# motor_kontrol_v1.net
KiCad netlist of a schematic drawn in EAGLE
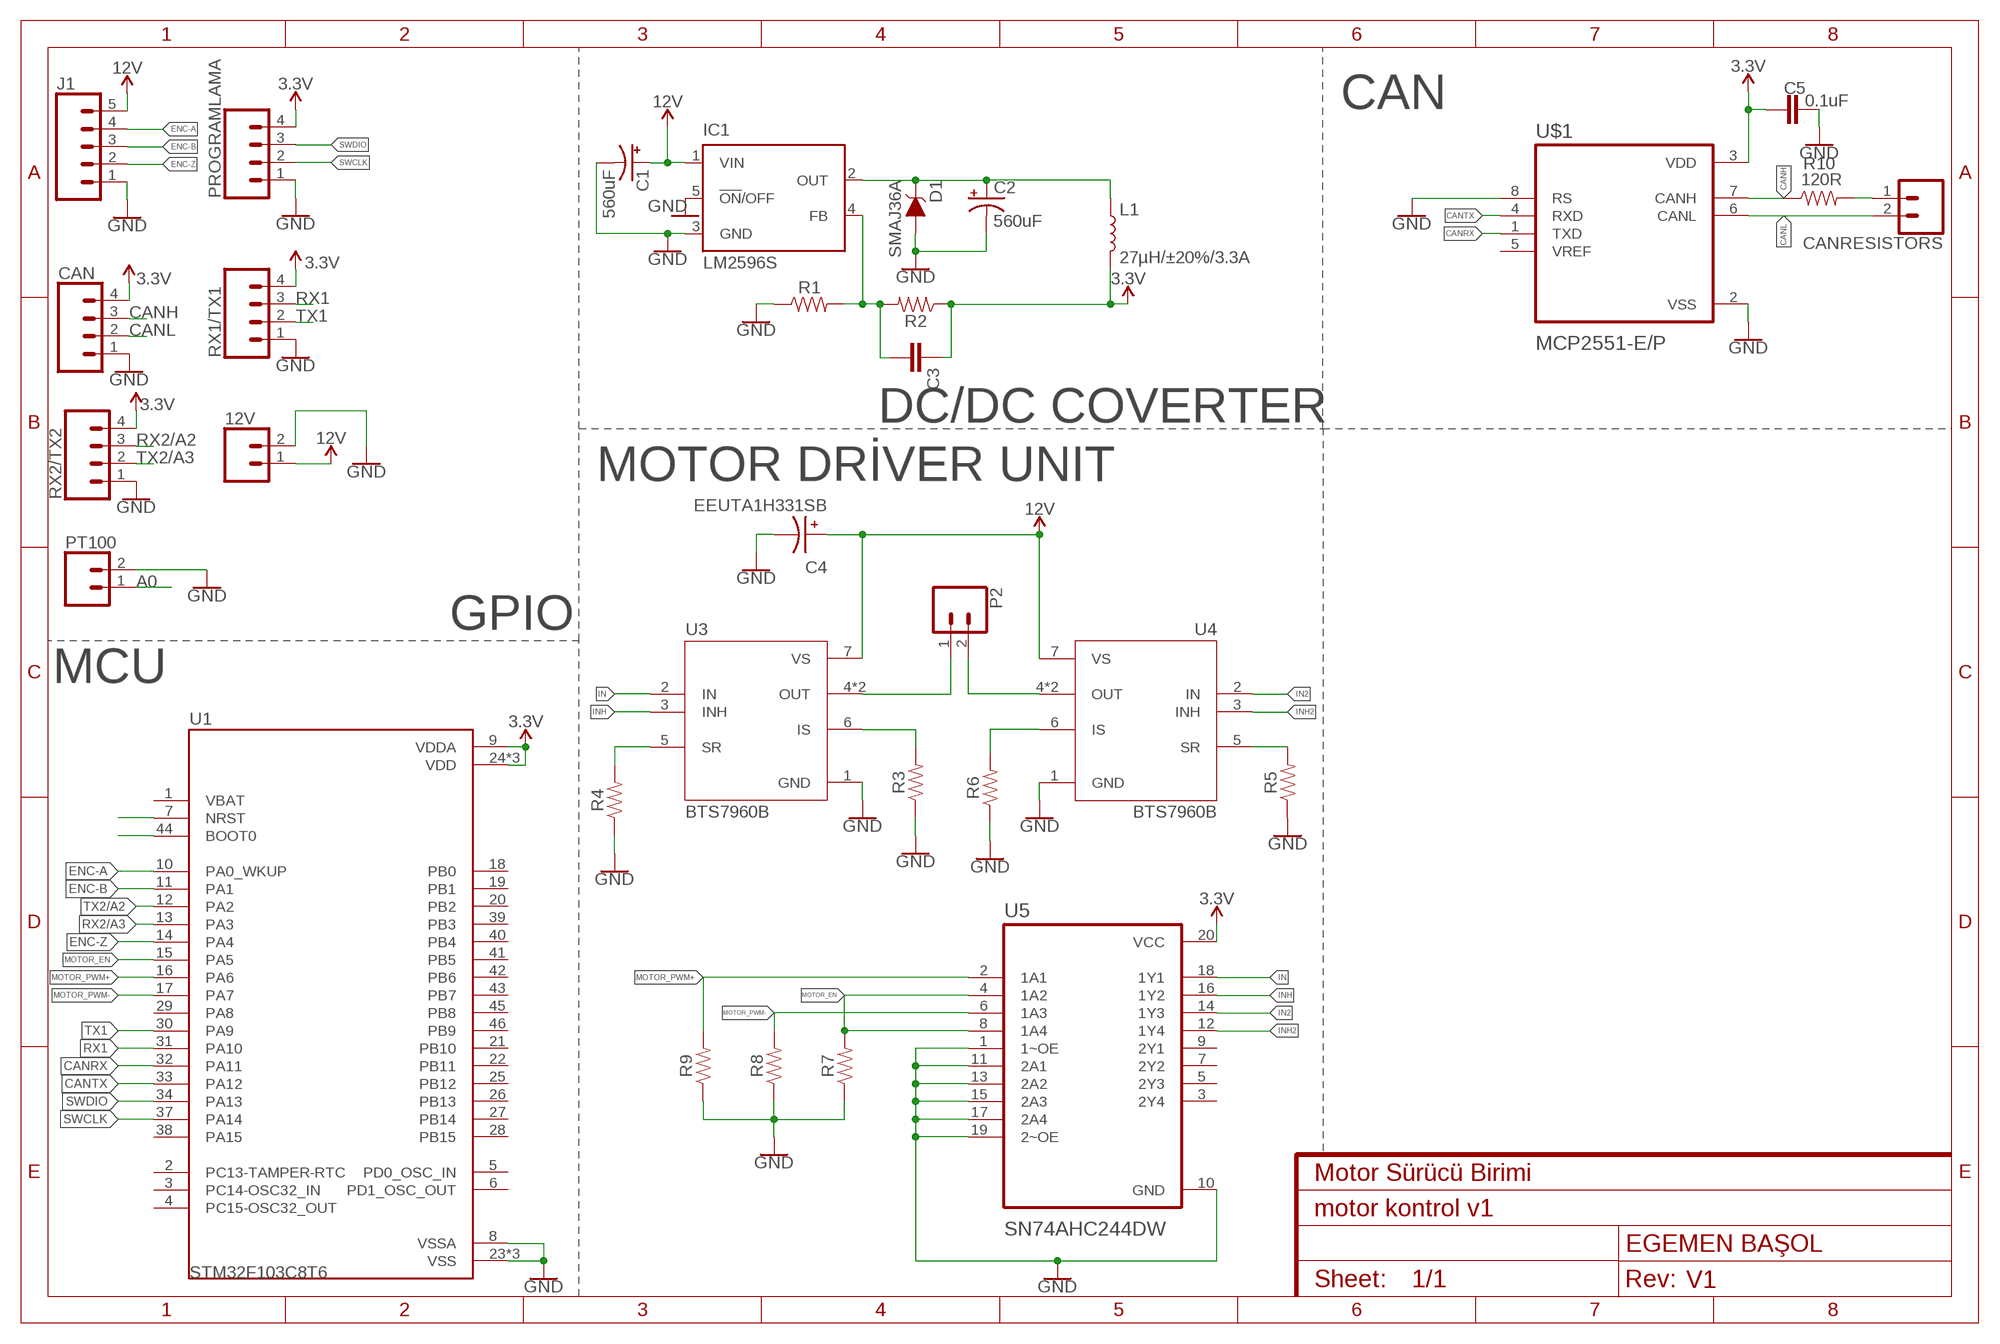
[diagram p0: schematic, sheet 1]

(export (version "E")
  (design (tool "Eeschema 10.0.6"))
  (components
    (comp (ref "12V")
      (value "CONN_023.5MM_LOCK")
      (footprint "eagle-import:SCREWTERMINAL-3.5MM-2_LOCK")
      (libsource (lib "eagle-import") (part "CONN_023.5MM_LOCK"))
    )
    (comp (ref "C1")
      (value "560uF")
      (footprint "eagle-import:PANASONIC_G")
      (libsource (lib "eagle-import") (part "560UF-PANASONIC_G-25V-20%"))
    )
    (comp (ref "C2")
      (value "560uF")
      (footprint "eagle-import:PANASONIC_G")
      (libsource (lib "eagle-import") (part "560UF-PANASONIC_G-25V-20%"))
    )
    (comp (ref "C3")
      (value "CAP-0805")
      (footprint "eagle-import:0805")
      (libsource (lib "eagle-import") (part "CAP-0805"))
    )
    (comp (ref "C4")
      (value "EEUTA1H331SB")
      (footprint "eagle-import:CAPPRD750W80D1600H1500")
      (fields (field (name "MF") "Panasonic"))
      (libsource (lib "eagle-import") (part "EEUTA1H331SB"))
    )
    (comp (ref "C5")
      (value "0.1uF")
      (footprint "eagle-import:0805")
      (libsource (lib "eagle-import") (part "CAP-0805"))
    )
    (comp (ref "CAN")
      (value "CONN_04SCREW_LOCK")
      (footprint "eagle-import:SCREWTERMINAL-3.5MM-4_LOCK")
      (libsource (lib "eagle-import") (part "CONN_04SCREW_LOCK"))
    )
    (comp (ref "CANRESISTORS")
      (value "CONN_02LOCK_LONGPADS")
      (footprint "eagle-import:1X02_LOCK_LONGPADS")
      (libsource (lib "eagle-import") (part "CONN_02LOCK_LONGPADS"))
    )
    (comp (ref "D1")
      (value "SMAJ36A")
      (footprint "eagle-import:DO-214AC")
      (libsource (lib "eagle-import") (part "DIODE_TVS_UNI"))
    )
    (comp (ref "IC1")
      (value "LM2596S")
      (footprint "eagle-import:TO263-5")
      (fields (field (name "MF") "NATIONAL SEMICONDUCTOR") (field (name "MPN") "LM2596S-ADJ/NOPB"))
      (libsource (lib "eagle-import") (part "LM2596S"))
    )
    (comp (ref "J1")
      (value "CONN_05SCREW")
      (footprint "eagle-import:SCREWTERMINAL-3.5MM-5")
      (libsource (lib "eagle-import") (part "CONN_05SCREW"))
    )
    (comp (ref "L1")
      (value "27µH/±20%/3.3A")
      (footprint "eagle-import:INDUCTOR_SDR1307")
      (libsource (lib "eagle-import") (part "INDUCTOR-SDR13-27UH"))
    )
    (comp (ref "P2")
      (value "CONN_023.5MM_LOCK")
      (footprint "eagle-import:SCREWTERMINAL-3.5MM-2_LOCK")
      (libsource (lib "eagle-import") (part "CONN_023.5MM_LOCK"))
    )
    (comp (ref "PROGRAMLAMA")
      (value "CONN_04SCREW_LOCK")
      (footprint "eagle-import:SCREWTERMINAL-3.5MM-4_LOCK")
      (libsource (lib "eagle-import") (part "CONN_04SCREW_LOCK"))
    )
    (comp (ref "PT100")
      (value "CONN_023.5MM_LOCK")
      (footprint "eagle-import:SCREWTERMINAL-3.5MM-2_LOCK")
      (libsource (lib "eagle-import") (part "CONN_023.5MM_LOCK"))
    )
    (comp (ref "R1")
      (value "RESISTOR0805")
      (footprint "eagle-import:0805")
      (libsource (lib "eagle-import") (part "RESISTOR0805"))
    )
    (comp (ref "R2")
      (value "RESISTOR0805")
      (footprint "eagle-import:0805")
      (libsource (lib "eagle-import") (part "RESISTOR0805"))
    )
    (comp (ref "R3")
      (value "RESISTOR0805")
      (footprint "eagle-import:0805")
      (libsource (lib "eagle-import") (part "RESISTOR0805"))
    )
    (comp (ref "R4")
      (value "RESISTOR0805")
      (footprint "eagle-import:0805")
      (libsource (lib "eagle-import") (part "RESISTOR0805"))
    )
    (comp (ref "R5")
      (value "RESISTOR0805")
      (footprint "eagle-import:0805")
      (libsource (lib "eagle-import") (part "RESISTOR0805"))
    )
    (comp (ref "R6")
      (value "RESISTOR0805")
      (footprint "eagle-import:0805")
      (libsource (lib "eagle-import") (part "RESISTOR0805"))
    )
    (comp (ref "R7")
      (value "RESISTOR0805")
      (footprint "eagle-import:0805")
      (libsource (lib "eagle-import") (part "RESISTOR0805"))
    )
    (comp (ref "R8")
      (value "RESISTOR0805")
      (footprint "eagle-import:0805")
      (libsource (lib "eagle-import") (part "RESISTOR0805"))
    )
    (comp (ref "R9")
      (value "RESISTOR0805")
      (footprint "eagle-import:0805")
      (libsource (lib "eagle-import") (part "RESISTOR0805"))
    )
    (comp (ref "R10")
      (value "120R")
      (footprint "eagle-import:0805")
      (libsource (lib "eagle-import") (part "RESISTOR0805"))
    )
    (comp (ref "RX1/TX1")
      (value "CONN_04SCREW_LOCK")
      (footprint "eagle-import:SCREWTERMINAL-3.5MM-4_LOCK")
      (libsource (lib "eagle-import") (part "CONN_04SCREW_LOCK"))
    )
    (comp (ref "RX2/TX2")
      (value "CONN_04SCREW_LOCK")
      (footprint "eagle-import:SCREWTERMINAL-3.5MM-4_LOCK")
      (libsource (lib "eagle-import") (part "CONN_04SCREW_LOCK"))
    )
    (comp (ref "U$1")
      (value "MCP2551-E/P")
      (footprint "eagle-import:DIP787W46P254L927H533Q8")
      (fields (field (name "MF") "Microchip"))
      (libsource (lib "eagle-import") (part "MCP2551-E/P"))
    )
    (comp (ref "U1")
      (value "STM32F103C8T6")
      (footprint "eagle-import:QFP50P900X900X160-48N")
      (fields (field (name "MF") "STMicroelectronics"))
      (libsource (lib "eagle-import") (part "STM32F103C8T6"))
    )
    (comp (ref "U3")
      (value "BTS7960B")
      (footprint "eagle-import:DPAK127P1490X440-8N")
      (fields (field (name "MF") "Infineon"))
      (libsource (lib "eagle-import") (part "BTS7960B"))
    )
    (comp (ref "U4")
      (value "BTS7960B")
      (footprint "eagle-import:DPAK127P1490X440-8N")
      (fields (field (name "MF") "Infineon"))
      (libsource (lib "eagle-import") (part "BTS7960B"))
    )
    (comp (ref "U5")
      (value "SN74AHC244DW")
      (footprint "eagle-import:SOIC127P1030X265-20N")
      (fields (field (name "MF") "Texas Instruments"))
      (libsource (lib "eagle-import") (part "SN74AHC244DW"))
    )
  )
  (nets
    (net (code "1") (name "/A0") (class "Default")
      (node (ref "PT100") (pin "1") (pinfunction "1_1") (pintype "passive"))
    )
    (net (code "2") (name "/RX2{slash}A2") (class "Default")
      (node (ref "RX2/TX2") (pin "3") (pinfunction "3_3") (pintype "passive"))
    )
    (net (code "3") (name "/TX2{slash}A3") (class "Default")
      (node (ref "RX2/TX2") (pin "2") (pinfunction "2_2") (pintype "passive"))
    )
    (net (code "4") (name "3.3V") (class "Default")
      (node (ref "C3") (pin "1") (pinfunction "1_1") (pintype "passive"))
      (node (ref "C5") (pin "2") (pinfunction "2_2") (pintype "passive"))
      (node (ref "CAN") (pin "4") (pinfunction "4_4") (pintype "passive"))
      (node (ref "L1") (pin "P$2") (pinfunction "2_P$2") (pintype "passive"))
      (node (ref "PROGRAMLAMA") (pin "4") (pinfunction "4_4") (pintype "passive"))
      (node (ref "R2") (pin "1") (pinfunction "1_1") (pintype "passive"))
      (node (ref "RX1/TX1") (pin "4") (pinfunction "4_4") (pintype "passive"))
      (node (ref "RX2/TX2") (pin "4") (pinfunction "4_4") (pintype "passive"))
      (node (ref "U$1") (pin "3") (pinfunction "VDD_3") (pintype "power_in"))
      (node (ref "U1") (pin "24") (pinfunction "VDD_24") (pintype "power_in"))
      (node (ref "U1") (pin "36") (pinfunction "VDD_36") (pintype "power_in"))
      (node (ref "U1") (pin "48") (pinfunction "VDD_48") (pintype "power_in"))
      (node (ref "U1") (pin "9") (pinfunction "VDDA_9") (pintype "power_in"))
      (node (ref "U5") (pin "20") (pinfunction "VCC_20") (pintype "power_in"))
    )
    (net (code "5") (name "12V") (class "Default")
      (node (ref "12V") (pin "1") (pinfunction "1_1") (pintype "passive"))
      (node (ref "C1") (pin "+") (pinfunction "+_+") (pintype "passive"))
      (node (ref "C4") (pin "P") (pinfunction "P_P") (pintype "passive"))
      (node (ref "IC1") (pin "1") (pinfunction "VIN_1") (pintype "input"))
      (node (ref "J1") (pin "5") (pinfunction "5_5") (pintype "passive"))
      (node (ref "U3") (pin "7") (pinfunction "VS_7") (pintype "power_in"))
      (node (ref "U4") (pin "7") (pinfunction "VS_7") (pintype "power_in"))
    )
    (net (code "6") (name "CANH") (class "Default")
      (node (ref "CAN") (pin "3") (pinfunction "3_3") (pintype "passive"))
      (node (ref "R10") (pin "1") (pinfunction "1_1") (pintype "passive"))
      (node (ref "U$1") (pin "7") (pinfunction "CANH_7") (pintype "output"))
    )
    (net (code "7") (name "CANL") (class "Default")
      (node (ref "CAN") (pin "2") (pinfunction "2_2") (pintype "passive"))
      (node (ref "CANRESISTORS") (pin "2") (pinfunction "2_2") (pintype "passive"))
      (node (ref "U$1") (pin "6") (pinfunction "CANL_6") (pintype "output"))
    )
    (net (code "8") (name "CANRX") (class "Default")
      (node (ref "U$1") (pin "1") (pinfunction "TXD_1") (pintype "input"))
      (node (ref "U1") (pin "32") (pinfunction "PA11_32") (pintype "bidirectional"))
    )
    (net (code "9") (name "CANTX") (class "Default")
      (node (ref "U$1") (pin "4") (pinfunction "RXD_4") (pintype "input"))
      (node (ref "U1") (pin "33") (pinfunction "PA12_33") (pintype "bidirectional"))
    )
    (net (code "10") (name "ENC-A") (class "Default")
      (node (ref "J1") (pin "4") (pinfunction "4_4") (pintype "passive"))
      (node (ref "U1") (pin "10") (pinfunction "PA0_WKUP_10") (pintype "bidirectional"))
    )
    (net (code "11") (name "ENC-B") (class "Default")
      (node (ref "J1") (pin "3") (pinfunction "3_3") (pintype "passive"))
      (node (ref "U1") (pin "11") (pinfunction "PA1_11") (pintype "bidirectional"))
    )
    (net (code "12") (name "ENC-Z") (class "Default")
      (node (ref "J1") (pin "2") (pinfunction "2_2") (pintype "passive"))
      (node (ref "U1") (pin "14") (pinfunction "PA4_14") (pintype "bidirectional"))
    )
    (net (code "13") (name "GND") (class "Default")
      (node (ref "12V") (pin "2") (pinfunction "2_2") (pintype "passive"))
      (node (ref "C1") (pin "-") (pinfunction "-_-") (pintype "passive"))
      (node (ref "C2") (pin "-") (pinfunction "-_-") (pintype "passive"))
      (node (ref "C4") (pin "N") (pinfunction "N_N") (pintype "passive"))
      (node (ref "C5") (pin "1") (pinfunction "1_1") (pintype "passive"))
      (node (ref "CAN") (pin "1") (pinfunction "1_1") (pintype "passive"))
      (node (ref "D1") (pin "A") (pinfunction "A_A") (pintype "passive"))
      (node (ref "IC1") (pin "3") (pinfunction "GND_3") (pintype "power_in"))
      (node (ref "IC1") (pin "5") (pinfunction "~{ON}/OFF_5") (pintype "input"))
      (node (ref "J1") (pin "1") (pinfunction "1_1") (pintype "passive"))
      (node (ref "PROGRAMLAMA") (pin "1") (pinfunction "1_1") (pintype "passive"))
      (node (ref "PT100") (pin "2") (pinfunction "2_2") (pintype "passive"))
      (node (ref "R1") (pin "1") (pinfunction "1_1") (pintype "passive"))
      (node (ref "R3") (pin "1") (pinfunction "1_1") (pintype "passive"))
      (node (ref "R4") (pin "1") (pinfunction "1_1") (pintype "passive"))
      (node (ref "R5") (pin "1") (pinfunction "1_1") (pintype "passive"))
      (node (ref "R6") (pin "1") (pinfunction "1_1") (pintype "passive"))
      (node (ref "R7") (pin "1") (pinfunction "1_1") (pintype "passive"))
      (node (ref "R8") (pin "1") (pinfunction "1_1") (pintype "passive"))
      (node (ref "R9") (pin "1") (pinfunction "1_1") (pintype "passive"))
      (node (ref "RX1/TX1") (pin "1") (pinfunction "1_1") (pintype "passive"))
      (node (ref "RX2/TX2") (pin "1") (pinfunction "1_1") (pintype "passive"))
      (node (ref "U$1") (pin "2") (pinfunction "VSS_2") (pintype "power_in"))
      (node (ref "U$1") (pin "8") (pinfunction "RS_8") (pintype "input"))
      (node (ref "U1") (pin "23") (pinfunction "VSS_23") (pintype "power_in"))
      (node (ref "U1") (pin "35") (pinfunction "VSS_35") (pintype "power_in"))
      (node (ref "U1") (pin "47") (pinfunction "VSS_47") (pintype "power_in"))
      (node (ref "U1") (pin "8") (pinfunction "VSSA_8") (pintype "power_in"))
      (node (ref "U3") (pin "1") (pinfunction "GND_1") (pintype "power_in"))
      (node (ref "U4") (pin "1") (pinfunction "GND_1") (pintype "power_in"))
      (node (ref "U5") (pin "1") (pinfunction "1~{OE}_1") (pintype "input"))
      (node (ref "U5") (pin "10") (pinfunction "GND_10") (pintype "power_in"))
      (node (ref "U5") (pin "11") (pinfunction "2A1_11") (pintype "input"))
      (node (ref "U5") (pin "13") (pinfunction "2A2_13") (pintype "input"))
      (node (ref "U5") (pin "15") (pinfunction "2A3_15") (pintype "input"))
      (node (ref "U5") (pin "17") (pinfunction "2A4_17") (pintype "input"))
      (node (ref "U5") (pin "19") (pinfunction "2~{OE}_19") (pintype "input"))
    )
    (net (code "14") (name "IN") (class "Default")
      (node (ref "U3") (pin "2") (pinfunction "IN_2") (pintype "input"))
      (node (ref "U5") (pin "18") (pinfunction "1Y1_18") (pintype "output"))
    )
    (net (code "15") (name "IN2") (class "Default")
      (node (ref "U4") (pin "2") (pinfunction "IN_2") (pintype "input"))
      (node (ref "U5") (pin "14") (pinfunction "1Y3_14") (pintype "output"))
    )
    (net (code "16") (name "INH") (class "Default")
      (node (ref "U3") (pin "3") (pinfunction "INH_3") (pintype "input"))
      (node (ref "U5") (pin "16") (pinfunction "1Y2_16") (pintype "output"))
    )
    (net (code "17") (name "INH2") (class "Default")
      (node (ref "U4") (pin "3") (pinfunction "INH_3") (pintype "input"))
      (node (ref "U5") (pin "12") (pinfunction "1Y4_12") (pintype "output"))
    )
    (net (code "18") (name "MOTOR_EN") (class "Default")
      (node (ref "R7") (pin "2") (pinfunction "2_2") (pintype "passive"))
      (node (ref "U1") (pin "15") (pinfunction "PA5_15") (pintype "bidirectional"))
      (node (ref "U5") (pin "4") (pinfunction "1A2_4") (pintype "input"))
      (node (ref "U5") (pin "8") (pinfunction "1A4_8") (pintype "input"))
    )
    (net (code "19") (name "MOTOR_PWM+") (class "Default")
      (node (ref "R9") (pin "2") (pinfunction "2_2") (pintype "passive"))
      (node (ref "U1") (pin "16") (pinfunction "PA6_16") (pintype "bidirectional"))
      (node (ref "U5") (pin "2") (pinfunction "1A1_2") (pintype "input"))
    )
    (net (code "20") (name "MOTOR_PWM-") (class "Default")
      (node (ref "R8") (pin "2") (pinfunction "2_2") (pintype "passive"))
      (node (ref "U1") (pin "17") (pinfunction "PA7_17") (pintype "bidirectional"))
      (node (ref "U5") (pin "6") (pinfunction "1A3_6") (pintype "input"))
    )
    (net (code "21") (name "Net-(CANRESISTORS-Pad1)") (class "Default")
      (node (ref "CANRESISTORS") (pin "1") (pinfunction "1_1") (pintype "passive"))
      (node (ref "R10") (pin "2") (pinfunction "2_2") (pintype "passive"))
    )
    (net (code "22") (name "Net-(IC1-FB)") (class "Default")
      (node (ref "C3") (pin "2") (pinfunction "2_2") (pintype "passive"))
      (node (ref "IC1") (pin "4") (pinfunction "FB_4") (pintype "input"))
      (node (ref "R1") (pin "2") (pinfunction "2_2") (pintype "passive"))
      (node (ref "R2") (pin "2") (pinfunction "2_2") (pintype "passive"))
    )
    (net (code "23") (name "Net-(IC1-OUT)") (class "Default")
      (node (ref "C2") (pin "+") (pinfunction "+_+") (pintype "passive"))
      (node (ref "D1") (pin "C") (pinfunction "C_C") (pintype "passive"))
      (node (ref "IC1") (pin "2") (pinfunction "OUT_2") (pintype "output"))
      (node (ref "L1") (pin "P$1") (pinfunction "1_P$1") (pintype "passive"))
    )
    (net (code "24") (name "Net-(P2-Pad1)") (class "Default")
      (node (ref "P2") (pin "1") (pinfunction "1_1") (pintype "passive"))
      (node (ref "U3") (pin "4") (pinfunction "OUT_4") (pintype "output"))
      (node (ref "U3") (pin "8") (pinfunction "OUT_8") (pintype "output"))
    )
    (net (code "25") (name "Net-(P2-Pad2)") (class "Default")
      (node (ref "P2") (pin "2") (pinfunction "2_2") (pintype "passive"))
      (node (ref "U4") (pin "4") (pinfunction "OUT_4") (pintype "output"))
      (node (ref "U4") (pin "8") (pinfunction "OUT_8") (pintype "output"))
    )
    (net (code "26") (name "Net-(U3-IS)") (class "Default")
      (node (ref "R3") (pin "2") (pinfunction "2_2") (pintype "passive"))
      (node (ref "U3") (pin "6") (pinfunction "IS_6") (pintype "output"))
    )
    (net (code "27") (name "Net-(U3-SR)") (class "Default")
      (node (ref "R4") (pin "2") (pinfunction "2_2") (pintype "passive"))
      (node (ref "U3") (pin "5") (pinfunction "SR_5") (pintype "input"))
    )
    (net (code "28") (name "Net-(U4-IS)") (class "Default")
      (node (ref "R6") (pin "2") (pinfunction "2_2") (pintype "passive"))
      (node (ref "U4") (pin "6") (pinfunction "IS_6") (pintype "output"))
    )
    (net (code "29") (name "Net-(U4-SR)") (class "Default")
      (node (ref "R5") (pin "2") (pinfunction "2_2") (pintype "passive"))
      (node (ref "U4") (pin "5") (pinfunction "SR_5") (pintype "input"))
    )
    (net (code "30") (name "RX1") (class "Default")
      (node (ref "RX1/TX1") (pin "3") (pinfunction "3_3") (pintype "passive"))
      (node (ref "U1") (pin "31") (pinfunction "PA10_31") (pintype "bidirectional"))
    )
    (net (code "31") (name "RX2{slash}A3") (class "Default")
      (node (ref "U1") (pin "13") (pinfunction "PA3_13") (pintype "bidirectional"))
    )
    (net (code "32") (name "SWCLK") (class "Default")
      (node (ref "PROGRAMLAMA") (pin "2") (pinfunction "2_2") (pintype "passive"))
      (node (ref "U1") (pin "37") (pinfunction "PA14_37") (pintype "bidirectional"))
    )
    (net (code "33") (name "SWDIO") (class "Default")
      (node (ref "PROGRAMLAMA") (pin "3") (pinfunction "3_3") (pintype "passive"))
      (node (ref "U1") (pin "34") (pinfunction "PA13_34") (pintype "bidirectional"))
    )
    (net (code "34") (name "TX1") (class "Default")
      (node (ref "RX1/TX1") (pin "2") (pinfunction "2_2") (pintype "passive"))
      (node (ref "U1") (pin "30") (pinfunction "PA9_30") (pintype "bidirectional"))
    )
    (net (code "35") (name "TX2{slash}A2") (class "Default")
      (node (ref "U1") (pin "12") (pinfunction "PA2_12") (pintype "bidirectional"))
    )
    (net (code "36") (name "unconnected-(U$1-VREF-Pad5)") (class "Default")
      (node (ref "U$1") (pin "5") (pinfunction "VREF_5") (pintype "input"))
    )
    (net (code "37") (name "unconnected-(U1-BOOT0-Pad44)") (class "Default")
      (node (ref "U1") (pin "44") (pinfunction "BOOT0_44") (pintype "input"))
    )
    (net (code "38") (name "unconnected-(U1-NRST-Pad7)") (class "Default")
      (node (ref "U1") (pin "7") (pinfunction "NRST_7") (pintype "input"))
    )
    (net (code "39") (name "unconnected-(U1-PA8-Pad29)") (class "Default")
      (node (ref "U1") (pin "29") (pinfunction "PA8_29") (pintype "bidirectional"))
    )
    (net (code "40") (name "unconnected-(U1-PA15-Pad38)") (class "Default")
      (node (ref "U1") (pin "38") (pinfunction "PA15_38") (pintype "bidirectional"))
    )
    (net (code "41") (name "unconnected-(U1-PB0-Pad18)") (class "Default")
      (node (ref "U1") (pin "18") (pinfunction "PB0_18") (pintype "bidirectional"))
    )
    (net (code "42") (name "unconnected-(U1-PB1-Pad19)") (class "Default")
      (node (ref "U1") (pin "19") (pinfunction "PB1_19") (pintype "bidirectional"))
    )
    (net (code "43") (name "unconnected-(U1-PB2-Pad20)") (class "Default")
      (node (ref "U1") (pin "20") (pinfunction "PB2_20") (pintype "bidirectional"))
    )
    (net (code "44") (name "unconnected-(U1-PB3-Pad39)") (class "Default")
      (node (ref "U1") (pin "39") (pinfunction "PB3_39") (pintype "bidirectional"))
    )
    (net (code "45") (name "unconnected-(U1-PB4-Pad40)") (class "Default")
      (node (ref "U1") (pin "40") (pinfunction "PB4_40") (pintype "bidirectional"))
    )
    (net (code "46") (name "unconnected-(U1-PB5-Pad41)") (class "Default")
      (node (ref "U1") (pin "41") (pinfunction "PB5_41") (pintype "bidirectional"))
    )
    (net (code "47") (name "unconnected-(U1-PB6-Pad42)") (class "Default")
      (node (ref "U1") (pin "42") (pinfunction "PB6_42") (pintype "bidirectional"))
    )
    (net (code "48") (name "unconnected-(U1-PB7-Pad43)") (class "Default")
      (node (ref "U1") (pin "43") (pinfunction "PB7_43") (pintype "bidirectional"))
    )
    (net (code "49") (name "unconnected-(U1-PB8-Pad45)") (class "Default")
      (node (ref "U1") (pin "45") (pinfunction "PB8_45") (pintype "bidirectional"))
    )
    (net (code "50") (name "unconnected-(U1-PB9-Pad46)") (class "Default")
      (node (ref "U1") (pin "46") (pinfunction "PB9_46") (pintype "bidirectional"))
    )
    (net (code "51") (name "unconnected-(U1-PB10-Pad21)") (class "Default")
      (node (ref "U1") (pin "21") (pinfunction "PB10_21") (pintype "bidirectional"))
    )
    (net (code "52") (name "unconnected-(U1-PB11-Pad22)") (class "Default")
      (node (ref "U1") (pin "22") (pinfunction "PB11_22") (pintype "bidirectional"))
    )
    (net (code "53") (name "unconnected-(U1-PB12-Pad25)") (class "Default")
      (node (ref "U1") (pin "25") (pinfunction "PB12_25") (pintype "bidirectional"))
    )
    (net (code "54") (name "unconnected-(U1-PB13-Pad26)") (class "Default")
      (node (ref "U1") (pin "26") (pinfunction "PB13_26") (pintype "bidirectional"))
    )
    (net (code "55") (name "unconnected-(U1-PB14-Pad27)") (class "Default")
      (node (ref "U1") (pin "27") (pinfunction "PB14_27") (pintype "bidirectional"))
    )
    (net (code "56") (name "unconnected-(U1-PB15-Pad28)") (class "Default")
      (node (ref "U1") (pin "28") (pinfunction "PB15_28") (pintype "bidirectional"))
    )
    (net (code "57") (name "unconnected-(U1-PC13-TAMPER-RTC-Pad2)") (class "Default")
      (node (ref "U1") (pin "2") (pinfunction "PC13-TAMPER-RTC_2") (pintype "bidirectional"))
    )
    (net (code "58") (name "unconnected-(U1-PC14-OSC32_IN-Pad3)") (class "Default")
      (node (ref "U1") (pin "3") (pinfunction "PC14-OSC32_IN_3") (pintype "bidirectional"))
    )
    (net (code "59") (name "unconnected-(U1-PC15-OSC32_OUT-Pad4)") (class "Default")
      (node (ref "U1") (pin "4") (pinfunction "PC15-OSC32_OUT_4") (pintype "bidirectional"))
    )
    (net (code "60") (name "unconnected-(U1-PD0_OSC_IN-Pad5)") (class "Default")
      (node (ref "U1") (pin "5") (pinfunction "PD0_OSC_IN_5") (pintype "bidirectional"))
    )
    (net (code "61") (name "unconnected-(U1-PD1_OSC_OUT-Pad6)") (class "Default")
      (node (ref "U1") (pin "6") (pinfunction "PD1_OSC_OUT_6") (pintype "bidirectional"))
    )
    (net (code "62") (name "unconnected-(U1-VBAT-Pad1)") (class "Default")
      (node (ref "U1") (pin "1") (pinfunction "VBAT_1") (pintype "bidirectional"))
    )
    (net (code "63") (name "unconnected-(U5-2Y1-Pad9)") (class "Default")
      (node (ref "U5") (pin "9") (pinfunction "2Y1_9") (pintype "output"))
    )
    (net (code "64") (name "unconnected-(U5-2Y2-Pad7)") (class "Default")
      (node (ref "U5") (pin "7") (pinfunction "2Y2_7") (pintype "output"))
    )
    (net (code "65") (name "unconnected-(U5-2Y3-Pad5)") (class "Default")
      (node (ref "U5") (pin "5") (pinfunction "2Y3_5") (pintype "output"))
    )
    (net (code "66") (name "unconnected-(U5-2Y4-Pad3)") (class "Default")
      (node (ref "U5") (pin "3") (pinfunction "2Y4_3") (pintype "output"))
    )
  )
)
